# Micro_V6.net
KiCad netlist of a schematic drawn in EAGLE
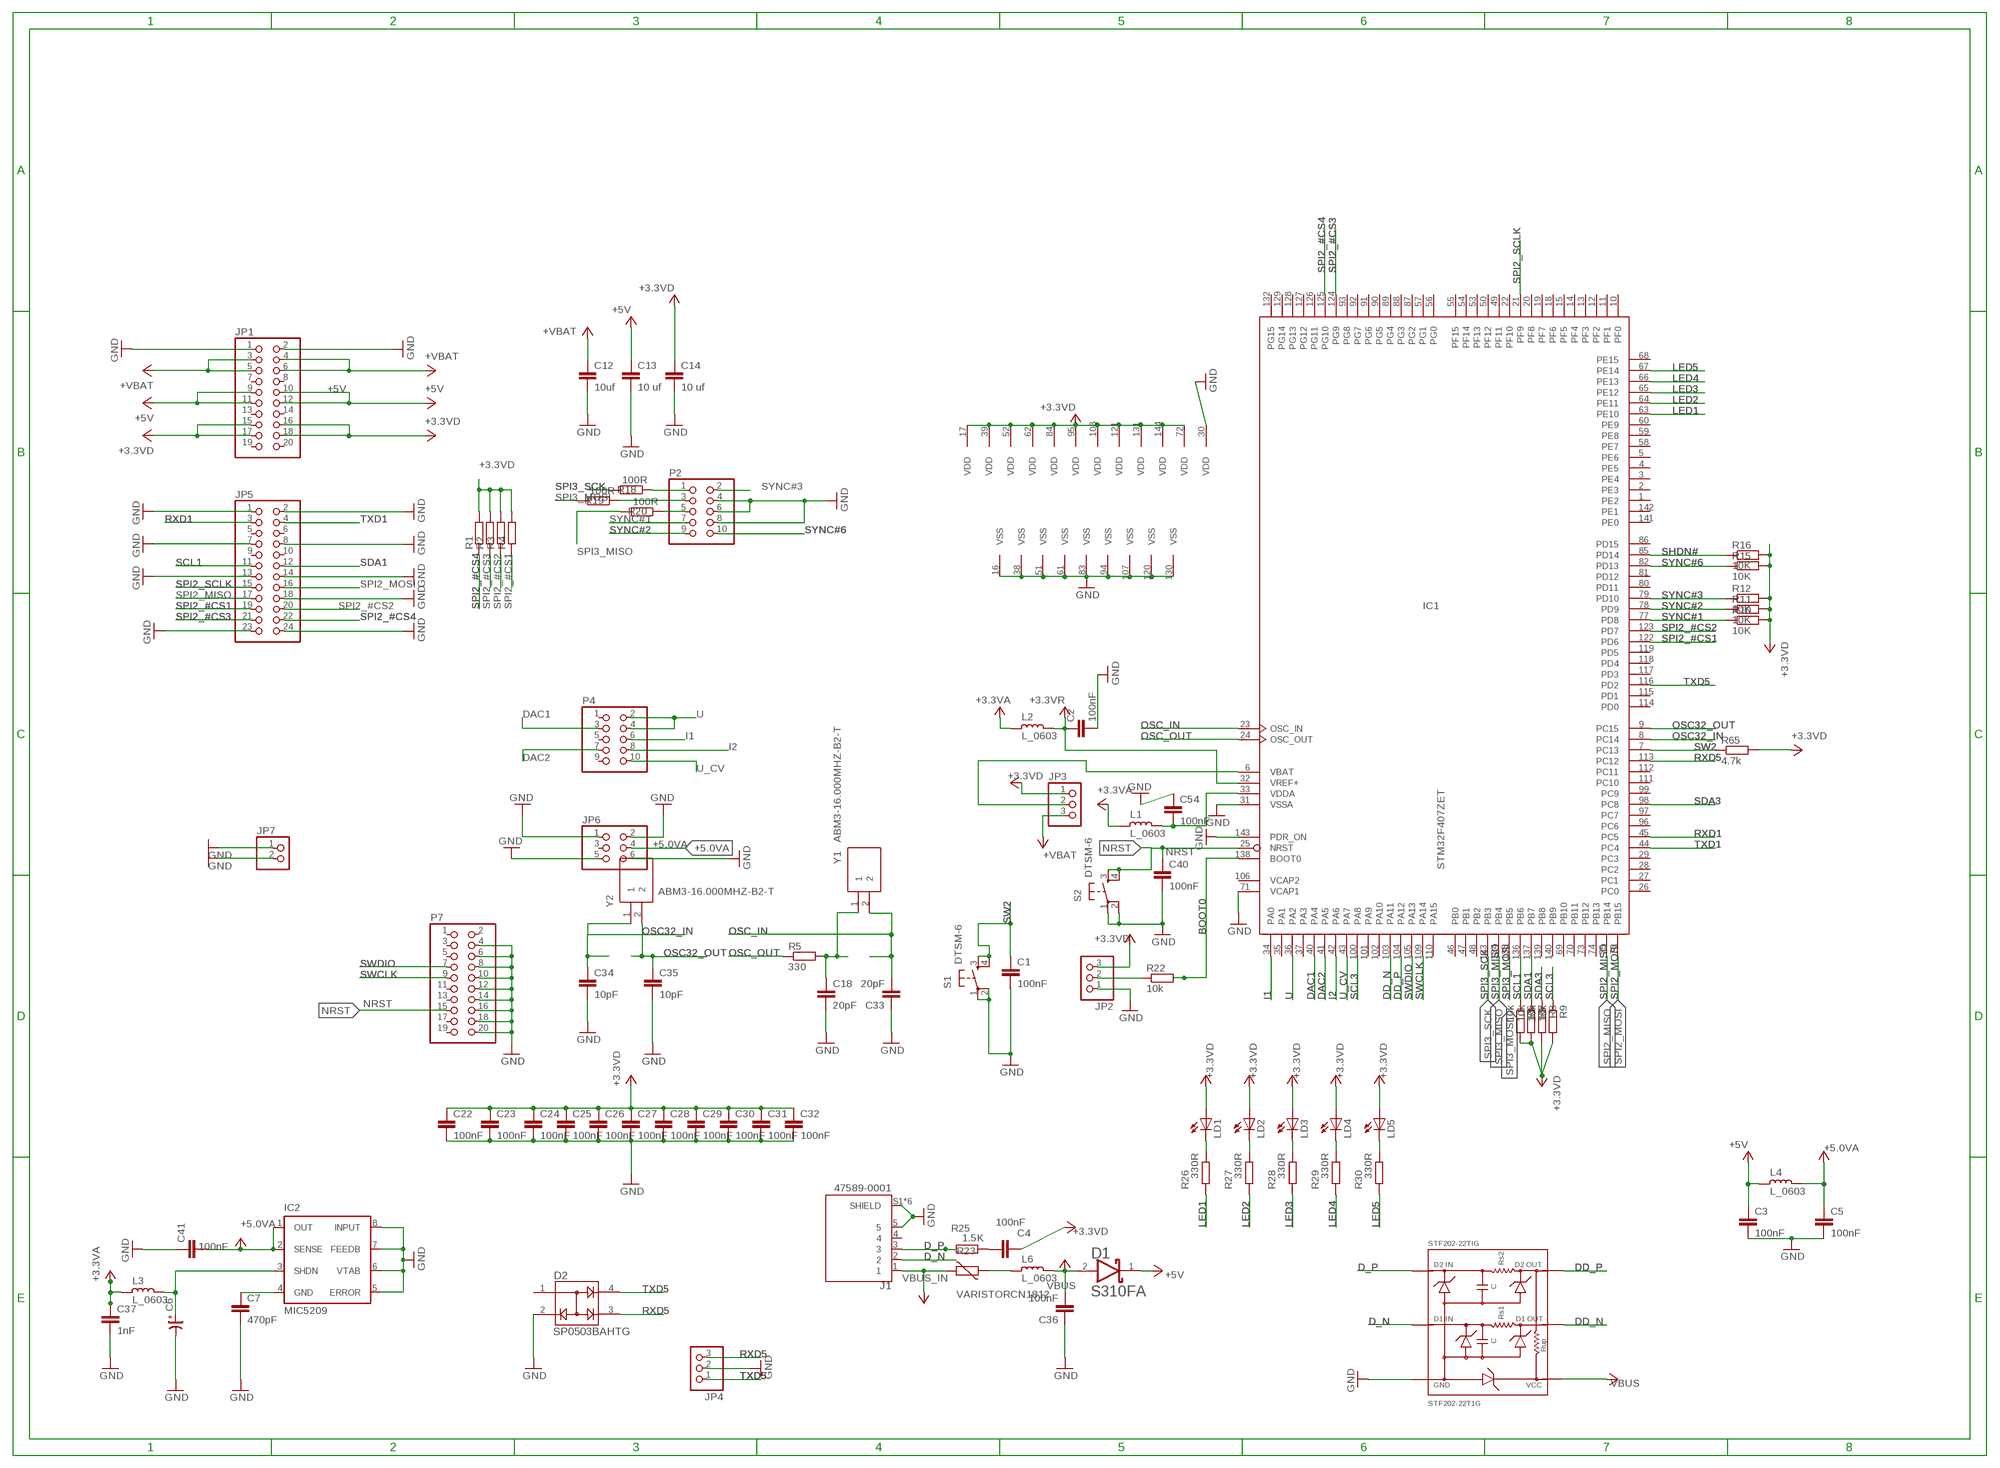
[diagram p0: schematic, sheet 1]

(export (version "E")
  (design (tool "Eeschema 10.0.6"))
  (components
    (comp (ref "C1")
      (value "100nF")
      (footprint "eagle-import:C0805")
      (libsource (lib "eagle-import") (part "C-EUC0805"))
    )
    (comp (ref "C2")
      (value "100nF")
      (footprint "eagle-import:C0805")
      (libsource (lib "eagle-import") (part "C-EUC0805"))
    )
    (comp (ref "C3")
      (value "100nF")
      (footprint "eagle-import:C0805")
      (libsource (lib "eagle-import") (part "C-EUC0805"))
    )
    (comp (ref "C4")
      (value "100nF")
      (footprint "eagle-import:C0805")
      (libsource (lib "eagle-import") (part "C-EUC0805"))
    )
    (comp (ref "C5")
      (value "100nF")
      (footprint "eagle-import:C0805")
      (libsource (lib "eagle-import") (part "C-EUC0805"))
    )
    (comp (ref "C6")
      (value "CP_SV-A")
      (footprint "eagle-import:CSV-A")
      (libsource (lib "eagle-import") (part "CP_SV-A"))
    )
    (comp (ref "C7")
      (value "470pF")
      (footprint "eagle-import:C0805")
      (libsource (lib "eagle-import") (part "C-EUC0805"))
    )
    (comp (ref "C12")
      (value "10uf")
      (footprint "eagle-import:C0805K")
      (libsource (lib "eagle-import") (part "C-EUC0805K"))
    )
    (comp (ref "C13")
      (value "10 uf")
      (footprint "eagle-import:C0805K")
      (libsource (lib "eagle-import") (part "C-EUC0805K"))
    )
    (comp (ref "C14")
      (value "10 uf")
      (footprint "eagle-import:C0805K")
      (libsource (lib "eagle-import") (part "C-EUC0805K"))
    )
    (comp (ref "C18")
      (value "20pF")
      (footprint "eagle-import:C0805")
      (libsource (lib "eagle-import") (part "C-EUC0805"))
    )
    (comp (ref "C22")
      (value "100nF")
      (footprint "eagle-import:C0805")
      (libsource (lib "eagle-import") (part "C-EUC0805"))
    )
    (comp (ref "C23")
      (value "100nF")
      (footprint "eagle-import:C0805")
      (libsource (lib "eagle-import") (part "C-EUC0805"))
    )
    (comp (ref "C24")
      (value "100nF")
      (footprint "eagle-import:C0805")
      (libsource (lib "eagle-import") (part "C-EUC0805"))
    )
    (comp (ref "C25")
      (value "100nF")
      (footprint "eagle-import:C0805")
      (libsource (lib "eagle-import") (part "C-EUC0805"))
    )
    (comp (ref "C26")
      (value "100nF")
      (footprint "eagle-import:C0805")
      (libsource (lib "eagle-import") (part "C-EUC0805"))
    )
    (comp (ref "C27")
      (value "100nF")
      (footprint "eagle-import:C0805")
      (libsource (lib "eagle-import") (part "C-EUC0805"))
    )
    (comp (ref "C28")
      (value "100nF")
      (footprint "eagle-import:C0805")
      (libsource (lib "eagle-import") (part "C-EUC0805"))
    )
    (comp (ref "C29")
      (value "100nF")
      (footprint "eagle-import:C0805")
      (libsource (lib "eagle-import") (part "C-EUC0805"))
    )
    (comp (ref "C30")
      (value "100nF")
      (footprint "eagle-import:C0805")
      (libsource (lib "eagle-import") (part "C-EUC0805"))
    )
    (comp (ref "C31")
      (value "100nF")
      (footprint "eagle-import:C0805")
      (libsource (lib "eagle-import") (part "C-EUC0805"))
    )
    (comp (ref "C32")
      (value "100nF")
      (footprint "eagle-import:C0805")
      (libsource (lib "eagle-import") (part "C-EUC0805"))
    )
    (comp (ref "C33")
      (value "20pF")
      (footprint "eagle-import:C0805")
      (libsource (lib "eagle-import") (part "C-EUC0805"))
    )
    (comp (ref "C34")
      (value "10pF")
      (footprint "eagle-import:C0805")
      (libsource (lib "eagle-import") (part "C-EUC0805"))
    )
    (comp (ref "C35")
      (value "10pF")
      (footprint "eagle-import:C0805")
      (libsource (lib "eagle-import") (part "C-EUC0805"))
    )
    (comp (ref "C36")
      (value "100nF")
      (footprint "eagle-import:C0805")
      (libsource (lib "eagle-import") (part "C-EUC0805"))
    )
    (comp (ref "C37")
      (value "1nF")
      (footprint "eagle-import:C0805")
      (libsource (lib "eagle-import") (part "C-EUC0805"))
    )
    (comp (ref "C40")
      (value "100nF")
      (footprint "eagle-import:C0805")
      (libsource (lib "eagle-import") (part "C-EUC0805"))
    )
    (comp (ref "C41")
      (value "100nF")
      (footprint "eagle-import:C0805")
      (libsource (lib "eagle-import") (part "C-EUC0805"))
    )
    (comp (ref "C54")
      (value "100nF")
      (footprint "eagle-import:C0805")
      (libsource (lib "eagle-import") (part "C-EUC0805"))
    )
    (comp (ref "D1")
      (value "ON_SEMICONDUCTOR_S310FAON_SEMICONDUCTOR_S310FA_0_0")
      (footprint "eagle-import:ON_SEMICONDUCTOR_S310FA_0")
      (fields
        (field (name "DIGIKEY_PART_NUMBER") "S310FACT-ND")
        (field (name "MF") "ON Semiconductor")
        (field (name "MOUSER_PART_NUMBER") "512-S310FA")
      )
      (libsource (lib "eagle-import") (part "ON_SEMICONDUCTOR_S310FAON_SEMICONDUCTOR_S310FA_0_0"))
    )
    (comp (ref "D2")
      (value "SP0503BAHTG")
      (footprint "eagle-import:SOT143")
      (fields (field (name "MF") "Littelfuse Inc."))
      (libsource (lib "eagle-import") (part "SP0503BAHTG"))
    )
    (comp (ref "IC1")
      (value "STM32F407ZET")
      (footprint "eagle-import:LQFP144")
      (libsource (lib "eagle-import") (part "STM32F407ZTE"))
    )
    (comp (ref "IC2")
      (value "MIC5209")
      (footprint "eagle-import:SO-08")
      (libsource (lib "eagle-import") (part "LP2951?ACM-3.3"))
    )
    (comp (ref "J1")
      (value "47589-0001")
      (footprint "eagle-import:MOLEX_47589-0001")
      (fields (field (name "MF") "Molex"))
      (libsource (lib "eagle-import") (part "47589-0001"))
    )
    (comp (ref "JP1")
      (value "PINHD-2X10")
      (footprint "eagle-import:2X10")
      (libsource (lib "eagle-import") (part "PINHD-2X10"))
    )
    (comp (ref "JP2")
      (value "PINHD-1X3")
      (footprint "eagle-import:1X03")
      (libsource (lib "eagle-import") (part "PINHD-1X3"))
    )
    (comp (ref "JP3")
      (value "PINHD-1X3")
      (footprint "eagle-import:1X03")
      (libsource (lib "eagle-import") (part "PINHD-1X3"))
    )
    (comp (ref "JP4")
      (value "PINHD-1X3")
      (footprint "eagle-import:1X03")
      (libsource (lib "eagle-import") (part "PINHD-1X3"))
    )
    (comp (ref "JP5")
      (value "PINHD-2X12")
      (footprint "eagle-import:2X12")
      (libsource (lib "eagle-import") (part "PINHD-2X12"))
    )
    (comp (ref "JP6")
      (value "PINHD-2X3")
      (footprint "eagle-import:2X03")
      (libsource (lib "eagle-import") (part "PINHD-2X3"))
    )
    (comp (ref "JP7")
      (value "PINHD-1X2")
      (footprint "eagle-import:1X02")
      (libsource (lib "eagle-import") (part "PINHD-1X2"))
    )
    (comp (ref "L1")
      (value "L_0603")
      (footprint "eagle-import:L0603")
      (libsource (lib "eagle-import") (part "L_0603"))
    )
    (comp (ref "L2")
      (value "L_0603")
      (footprint "eagle-import:L0603")
      (libsource (lib "eagle-import") (part "L_0603"))
    )
    (comp (ref "L3")
      (value "L_0603")
      (footprint "eagle-import:L0603")
      (libsource (lib "eagle-import") (part "L_0603"))
    )
    (comp (ref "L4")
      (value "L_0603")
      (footprint "eagle-import:L0603")
      (libsource (lib "eagle-import") (part "L_0603"))
    )
    (comp (ref "L6")
      (value "L_0603")
      (footprint "eagle-import:L0603")
      (libsource (lib "eagle-import") (part "L_0603"))
    )
    (comp (ref "LD1")
      (value "LEDSMT1206")
      (footprint "eagle-import:1206")
      (libsource (lib "eagle-import") (part "LEDSMT1206"))
    )
    (comp (ref "LD2")
      (value "LEDSMT1206")
      (footprint "eagle-import:1206")
      (libsource (lib "eagle-import") (part "LEDSMT1206"))
    )
    (comp (ref "LD3")
      (value "LEDSMT1206")
      (footprint "eagle-import:1206")
      (libsource (lib "eagle-import") (part "LEDSMT1206"))
    )
    (comp (ref "LD4")
      (value "LEDSMT1206")
      (footprint "eagle-import:1206")
      (libsource (lib "eagle-import") (part "LEDSMT1206"))
    )
    (comp (ref "LD5")
      (value "LEDSMT1206")
      (footprint "eagle-import:1206")
      (libsource (lib "eagle-import") (part "LEDSMT1206"))
    )
    (comp (ref "P2")
      (value "PINHD-2X5")
      (footprint "eagle-import:2X05")
      (libsource (lib "eagle-import") (part "PINHD-2X5"))
    )
    (comp (ref "P4")
      (value "PINHD-2X5")
      (footprint "eagle-import:2X05")
      (libsource (lib "eagle-import") (part "PINHD-2X5"))
    )
    (comp (ref "P7")
      (value "PINHD-2X10")
      (footprint "eagle-import:2X10")
      (libsource (lib "eagle-import") (part "PINHD-2X10"))
    )
    (comp (ref "R1")
      (value "R-EU_R0603")
      (footprint "eagle-import:R0603")
      (libsource (lib "eagle-import") (part "R-EU_R0603"))
    )
    (comp (ref "R2")
      (value "R-EU_R0603")
      (footprint "eagle-import:R0603")
      (libsource (lib "eagle-import") (part "R-EU_R0603"))
    )
    (comp (ref "R3")
      (value "R-EU_R0603")
      (footprint "eagle-import:R0603")
      (libsource (lib "eagle-import") (part "R-EU_R0603"))
    )
    (comp (ref "R4")
      (value "R-EU_R0603")
      (footprint "eagle-import:R0603")
      (libsource (lib "eagle-import") (part "R-EU_R0603"))
    )
    (comp (ref "R5")
      (value "330")
      (footprint "eagle-import:R0603")
      (libsource (lib "eagle-import") (part "R-EU_R0603"))
    )
    (comp (ref "R6")
      (value "10k")
      (footprint "eagle-import:R0603")
      (libsource (lib "eagle-import") (part "R-EU_R0603"))
    )
    (comp (ref "R7")
      (value "10k")
      (footprint "eagle-import:R0603")
      (libsource (lib "eagle-import") (part "R-EU_R0603"))
    )
    (comp (ref "R8")
      (value "10k")
      (footprint "eagle-import:R0603")
      (libsource (lib "eagle-import") (part "R-EU_R0603"))
    )
    (comp (ref "R9")
      (value "10k")
      (footprint "eagle-import:R0603")
      (libsource (lib "eagle-import") (part "R-EU_R0603"))
    )
    (comp (ref "R10")
      (value "10K")
      (footprint "eagle-import:R0603")
      (libsource (lib "eagle-import") (part "R-EU_R0603"))
    )
    (comp (ref "R11")
      (value "10K")
      (footprint "eagle-import:R0603")
      (libsource (lib "eagle-import") (part "R-EU_R0603"))
    )
    (comp (ref "R12")
      (value "10K")
      (footprint "eagle-import:R0603")
      (libsource (lib "eagle-import") (part "R-EU_R0603"))
    )
    (comp (ref "R15")
      (value "10K")
      (footprint "eagle-import:R0603")
      (libsource (lib "eagle-import") (part "R-EU_R0603"))
    )
    (comp (ref "R16")
      (value "10K")
      (footprint "eagle-import:R0603")
      (libsource (lib "eagle-import") (part "R-EU_R0603"))
    )
    (comp (ref "R18")
      (value "100R")
      (footprint "eagle-import:R0603")
      (libsource (lib "eagle-import") (part "R-EU_R0603"))
    )
    (comp (ref "R19")
      (value "100R")
      (footprint "eagle-import:R0603")
      (libsource (lib "eagle-import") (part "R-EU_R0603"))
    )
    (comp (ref "R20")
      (value "100R")
      (footprint "eagle-import:R0603")
      (libsource (lib "eagle-import") (part "R-EU_R0603"))
    )
    (comp (ref "R22")
      (value "10k")
      (footprint "eagle-import:R0603")
      (libsource (lib "eagle-import") (part "R-EU_R0603"))
    )
    (comp (ref "R23")
      (value "VARISTORCN1812")
      (footprint "eagle-import:CT_CN1812")
      (libsource (lib "eagle-import") (part "VARISTORCN1812"))
    )
    (comp (ref "R25")
      (value "1.5K")
      (footprint "eagle-import:R0603")
      (libsource (lib "eagle-import") (part "R-EU_R0603"))
    )
    (comp (ref "R26")
      (value "330R")
      (footprint "eagle-import:R0603")
      (libsource (lib "eagle-import") (part "R-EU_R0603"))
    )
    (comp (ref "R27")
      (value "330R")
      (footprint "eagle-import:R0603")
      (libsource (lib "eagle-import") (part "R-EU_R0603"))
    )
    (comp (ref "R28")
      (value "330R")
      (footprint "eagle-import:R0603")
      (libsource (lib "eagle-import") (part "R-EU_R0603"))
    )
    (comp (ref "R29")
      (value "330R")
      (footprint "eagle-import:R0603")
      (libsource (lib "eagle-import") (part "R-EU_R0603"))
    )
    (comp (ref "R30")
      (value "330R")
      (footprint "eagle-import:R0603")
      (libsource (lib "eagle-import") (part "R-EU_R0603"))
    )
    (comp (ref "R65")
      (value "4.7k")
      (footprint "eagle-import:R0603")
      (libsource (lib "eagle-import") (part "R-EU_R0603"))
    )
    (comp (ref "S1")
      (value "DTSM-6")
      (footprint "eagle-import:DTSM-6")
      (libsource (lib "eagle-import") (part "DTSM-6"))
    )
    (comp (ref "S2")
      (value "DTSM-6")
      (footprint "eagle-import:DTSM-6")
      (libsource (lib "eagle-import") (part "DTSM-6"))
    )
    (comp (ref "STF202-22TIG")
      (value "STF202-22T1G")
      (footprint "eagle-import:STF202-22T1G")
      (fields (field (name "MF") "ON Semiconductor"))
      (libsource (lib "eagle-import") (part "STF202-22T1G"))
    )
    (comp (ref "Y1")
      (value "ABM3-16.000MHZ-B2-T")
      (footprint "eagle-import:ABM316000MHZB2T")
      (fields (field (name "MOUSER_PART_NUMBER") "815-ABM3-16-B2-T"))
      (libsource (lib "eagle-import") (part "ABM3-16.000MHZ-B2-T"))
    )
    (comp (ref "Y2")
      (value "ABM3-16.000MHZ-B2-T")
      (footprint "eagle-import:ABM316000MHZB2T")
      (fields (field (name "MOUSER_PART_NUMBER") "815-ABM3-16-B2-T"))
      (libsource (lib "eagle-import") (part "ABM3-16.000MHZ-B2-T"))
    )
  )
  (nets
    (net (code "1") (name "+3.3VA") (class "Default")
      (node (ref "C37") (pin "1") (pinfunction "1_1") (pintype "passive"))
      (node (ref "L1") (pin "2") (pinfunction "2_2") (pintype "passive"))
      (node (ref "L2") (pin "2") (pinfunction "2_2") (pintype "passive"))
      (node (ref "L3") (pin "2") (pinfunction "2_2") (pintype "passive"))
    )
    (net (code "2") (name "+3.3VD") (class "Default")
      (node (ref "C14") (pin "1") (pinfunction "1_1") (pintype "passive"))
      (node (ref "C22") (pin "1") (pinfunction "1_1") (pintype "passive"))
      (node (ref "C23") (pin "1") (pinfunction "1_1") (pintype "passive"))
      (node (ref "C24") (pin "1") (pinfunction "1_1") (pintype "passive"))
      (node (ref "C25") (pin "1") (pinfunction "1_1") (pintype "passive"))
      (node (ref "C26") (pin "1") (pinfunction "1_1") (pintype "passive"))
      (node (ref "C27") (pin "1") (pinfunction "1_1") (pintype "passive"))
      (node (ref "C28") (pin "1") (pinfunction "1_1") (pintype "passive"))
      (node (ref "C29") (pin "1") (pinfunction "1_1") (pintype "passive"))
      (node (ref "C30") (pin "1") (pinfunction "1_1") (pintype "passive"))
      (node (ref "C31") (pin "1") (pinfunction "1_1") (pintype "passive"))
      (node (ref "C32") (pin "1") (pinfunction "1_1") (pintype "passive"))
      (node (ref "C4") (pin "1") (pinfunction "1_1") (pintype "passive"))
      (node (ref "IC1") (pin "108") (pinfunction "VDD_108") (pintype "power_in"))
      (node (ref "IC1") (pin "121") (pinfunction "VDD_121") (pintype "power_in"))
      (node (ref "IC1") (pin "131") (pinfunction "VDD_131") (pintype "power_in"))
      (node (ref "IC1") (pin "144") (pinfunction "VDD_144") (pintype "power_in"))
      (node (ref "IC1") (pin "17") (pinfunction "VDD_17") (pintype "power_in"))
      (node (ref "IC1") (pin "39") (pinfunction "VDD_39") (pintype "power_in"))
      (node (ref "IC1") (pin "52") (pinfunction "VDD_52") (pintype "power_in"))
      (node (ref "IC1") (pin "62") (pinfunction "VDD_62") (pintype "power_in"))
      (node (ref "IC1") (pin "72") (pinfunction "VDD_72") (pintype "power_in"))
      (node (ref "IC1") (pin "84") (pinfunction "VDD_84") (pintype "power_in"))
      (node (ref "IC1") (pin "95") (pinfunction "VDD_95") (pintype "power_in"))
      (node (ref "JP1") (pin "15") (pinfunction "15_15") (pintype "passive"))
      (node (ref "JP1") (pin "16") (pinfunction "16_16") (pintype "passive"))
      (node (ref "JP1") (pin "17") (pinfunction "17_17") (pintype "passive"))
      (node (ref "JP1") (pin "18") (pinfunction "18_18") (pintype "passive"))
      (node (ref "JP2") (pin "3") (pinfunction "3_3") (pintype "passive"))
      (node (ref "JP3") (pin "1") (pinfunction "1_1") (pintype "passive"))
      (node (ref "LD1") (pin "A") (pinfunction "A_A") (pintype "passive"))
      (node (ref "LD2") (pin "A") (pinfunction "A_A") (pintype "passive"))
      (node (ref "LD3") (pin "A") (pinfunction "A_A") (pintype "passive"))
      (node (ref "LD4") (pin "A") (pinfunction "A_A") (pintype "passive"))
      (node (ref "LD5") (pin "A") (pinfunction "A_A") (pintype "passive"))
      (node (ref "R1") (pin "2") (pinfunction "2_2") (pintype "passive"))
      (node (ref "R10") (pin "2") (pinfunction "2_2") (pintype "passive"))
      (node (ref "R11") (pin "2") (pinfunction "2_2") (pintype "passive"))
      (node (ref "R12") (pin "2") (pinfunction "2_2") (pintype "passive"))
      (node (ref "R15") (pin "2") (pinfunction "2_2") (pintype "passive"))
      (node (ref "R16") (pin "2") (pinfunction "2_2") (pintype "passive"))
      (node (ref "R2") (pin "2") (pinfunction "2_2") (pintype "passive"))
      (node (ref "R3") (pin "2") (pinfunction "2_2") (pintype "passive"))
      (node (ref "R4") (pin "2") (pinfunction "2_2") (pintype "passive"))
      (node (ref "R6") (pin "2") (pinfunction "2_2") (pintype "passive"))
      (node (ref "R65") (pin "2") (pinfunction "2_2") (pintype "passive"))
      (node (ref "R7") (pin "2") (pinfunction "2_2") (pintype "passive"))
      (node (ref "R8") (pin "2") (pinfunction "2_2") (pintype "passive"))
      (node (ref "R9") (pin "2") (pinfunction "2_2") (pintype "passive"))
    )
    (net (code "3") (name "+3.3VR") (class "Default")
      (node (ref "C2") (pin "1") (pinfunction "1_1") (pintype "passive"))
      (node (ref "IC1") (pin "32") (pinfunction "VREF+_32") (pintype "power_in"))
      (node (ref "L2") (pin "1") (pinfunction "1_1") (pintype "passive"))
    )
    (net (code "4") (name "+5.0VA") (class "Default")
      (node (ref "C41") (pin "2") (pinfunction "2_2") (pintype "passive"))
      (node (ref "C5") (pin "1") (pinfunction "1_1") (pintype "passive"))
      (node (ref "IC2") (pin "1") (pinfunction "OUT_1") (pintype "output"))
      (node (ref "IC2") (pin "2") (pinfunction "SENSE_2") (pintype "input"))
      (node (ref "JP6") (pin "4") (pinfunction "4_4") (pintype "passive"))
      (node (ref "L4") (pin "1") (pinfunction "1_1") (pintype "passive"))
    )
    (net (code "5") (name "+5V") (class "Default")
      (node (ref "C13") (pin "1") (pinfunction "1_1") (pintype "passive"))
      (node (ref "C3") (pin "1") (pinfunction "1_1") (pintype "passive"))
      (node (ref "D1") (pin "1") (pinfunction "CATHODE_1") (pintype "passive"))
      (node (ref "JP1") (pin "10") (pinfunction "10_10") (pintype "passive"))
      (node (ref "JP1") (pin "11") (pinfunction "11_11") (pintype "passive"))
      (node (ref "JP1") (pin "12") (pinfunction "12_12") (pintype "passive"))
      (node (ref "JP1") (pin "9") (pinfunction "9_9") (pintype "passive"))
      (node (ref "L4") (pin "2") (pinfunction "2_2") (pintype "passive"))
    )
    (net (code "6") (name "+VBAT") (class "Default")
      (node (ref "C12") (pin "1") (pinfunction "1_1") (pintype "passive"))
      (node (ref "JP1") (pin "3") (pinfunction "3_3") (pintype "passive"))
      (node (ref "JP1") (pin "4") (pinfunction "4_4") (pintype "passive"))
      (node (ref "JP1") (pin "5") (pinfunction "5_5") (pintype "passive"))
      (node (ref "JP1") (pin "6") (pinfunction "6_6") (pintype "passive"))
      (node (ref "JP3") (pin "3") (pinfunction "3_3") (pintype "passive"))
    )
    (net (code "7") (name "/BOOT0") (class "Default")
      (node (ref "IC1") (pin "138") (pinfunction "BOOT0_138") (pintype "input"))
      (node (ref "R22") (pin "2") (pinfunction "2_2") (pintype "passive"))
    )
    (net (code "8") (name "/DAC1") (class "Default")
      (node (ref "IC1") (pin "40") (pinfunction "PA4_40") (pintype "bidirectional"))
      (node (ref "P4") (pin "3") (pinfunction "3_3") (pintype "passive"))
    )
    (net (code "9") (name "/DAC2") (class "Default")
      (node (ref "IC1") (pin "41") (pinfunction "PA5_41") (pintype "bidirectional"))
      (node (ref "P4") (pin "7") (pinfunction "7_7") (pintype "passive"))
    )
    (net (code "10") (name "/DD_N") (class "Default")
      (node (ref "IC1") (pin "103") (pinfunction "PA11_103") (pintype "bidirectional"))
      (node (ref "STF202-22TIG") (pin "2") (pinfunction "D1-IN_2") (pintype "bidirectional"))
    )
    (net (code "11") (name "/DD_P") (class "Default")
      (node (ref "IC1") (pin "104") (pinfunction "PA12_104") (pintype "bidirectional"))
      (node (ref "STF202-22TIG") (pin "3") (pinfunction "D2-IN_3") (pintype "bidirectional"))
    )
    (net (code "12") (name "/D_N") (class "Default")
      (node (ref "J1") (pin "2") (pinfunction "2_2") (pintype "passive"))
      (node (ref "STF202-22TIG") (pin "5") (pinfunction "D1-OUT_5") (pintype "bidirectional"))
    )
    (net (code "13") (name "/D_P") (class "Default")
      (node (ref "J1") (pin "3") (pinfunction "3_3") (pintype "passive"))
      (node (ref "R25") (pin "1") (pinfunction "1_1") (pintype "passive"))
      (node (ref "STF202-22TIG") (pin "4") (pinfunction "D2-OUT_4") (pintype "bidirectional"))
    )
    (net (code "14") (name "/I1") (class "Default")
      (node (ref "IC1") (pin "34") (pinfunction "PA0_34") (pintype "bidirectional"))
      (node (ref "P4") (pin "6") (pinfunction "6_6") (pintype "passive"))
    )
    (net (code "15") (name "/I2") (class "Default")
      (node (ref "IC1") (pin "42") (pinfunction "PA6_42") (pintype "bidirectional"))
      (node (ref "P4") (pin "8") (pinfunction "8_8") (pintype "passive"))
    )
    (net (code "16") (name "/LED1") (class "Default")
      (node (ref "IC1") (pin "63") (pinfunction "PE10_63") (pintype "bidirectional"))
      (node (ref "R26") (pin "1") (pinfunction "1_1") (pintype "passive"))
    )
    (net (code "17") (name "/LED2") (class "Default")
      (node (ref "IC1") (pin "64") (pinfunction "PE11_64") (pintype "bidirectional"))
      (node (ref "R27") (pin "1") (pinfunction "1_1") (pintype "passive"))
    )
    (net (code "18") (name "/LED3") (class "Default")
      (node (ref "IC1") (pin "65") (pinfunction "PE12_65") (pintype "bidirectional"))
      (node (ref "R28") (pin "1") (pinfunction "1_1") (pintype "passive"))
    )
    (net (code "19") (name "/LED4") (class "Default")
      (node (ref "IC1") (pin "66") (pinfunction "PE13_66") (pintype "bidirectional"))
      (node (ref "R29") (pin "1") (pinfunction "1_1") (pintype "passive"))
    )
    (net (code "20") (name "/LED5") (class "Default")
      (node (ref "IC1") (pin "67") (pinfunction "PE14_67") (pintype "bidirectional"))
      (node (ref "R30") (pin "1") (pinfunction "1_1") (pintype "passive"))
    )
    (net (code "21") (name "/OSC32_IN") (class "Default")
      (node (ref "C34") (pin "1") (pinfunction "1_1") (pintype "passive"))
      (node (ref "IC1") (pin "8") (pinfunction "PC14_8") (pintype "bidirectional"))
      (node (ref "Y2") (pin "1") (pinfunction "1_1") (pintype "bidirectional"))
    )
    (net (code "22") (name "/OSC32_OUT") (class "Default")
      (node (ref "C35") (pin "1") (pinfunction "1_1") (pintype "passive"))
      (node (ref "IC1") (pin "9") (pinfunction "PC15_9") (pintype "bidirectional"))
      (node (ref "Y2") (pin "2") (pinfunction "2_2") (pintype "bidirectional"))
    )
    (net (code "23") (name "/OSC_IN") (class "Default")
      (node (ref "C33") (pin "2") (pinfunction "2_2") (pintype "passive"))
      (node (ref "IC1") (pin "23") (pinfunction "OSC_IN_23") (pintype "bidirectional"))
      (node (ref "Y1") (pin "2") (pinfunction "2_2") (pintype "bidirectional"))
    )
    (net (code "24") (name "/OSC_OUT") (class "Default")
      (node (ref "IC1") (pin "24") (pinfunction "OSC_OUT_24") (pintype "bidirectional"))
      (node (ref "R5") (pin "1") (pinfunction "1_1") (pintype "passive"))
    )
    (net (code "25") (name "/RXD1") (class "Default")
      (node (ref "IC1") (pin "45") (pinfunction "PC5_45") (pintype "bidirectional"))
      (node (ref "JP5") (pin "3") (pinfunction "3_3") (pintype "passive"))
    )
    (net (code "26") (name "/RXD5") (class "Default")
      (node (ref "D2") (pin "3") (pinfunction "3_3") (pintype "passive"))
      (node (ref "IC1") (pin "113") (pinfunction "PC12_113") (pintype "bidirectional"))
      (node (ref "JP4") (pin "3") (pinfunction "3_3") (pintype "passive"))
    )
    (net (code "27") (name "/SCL1") (class "Default")
      (node (ref "IC1") (pin "136") (pinfunction "PB6_136") (pintype "bidirectional"))
      (node (ref "JP5") (pin "11") (pinfunction "11_11") (pintype "passive"))
      (node (ref "R6") (pin "1") (pinfunction "1_1") (pintype "passive"))
    )
    (net (code "28") (name "/SCL3") (class "Default")
      (node (ref "IC1") (pin "100") (pinfunction "PA8_100") (pintype "bidirectional"))
      (node (ref "R9") (pin "1") (pinfunction "1_1") (pintype "passive"))
    )
    (net (code "29") (name "/SDA1") (class "Default")
      (node (ref "IC1") (pin "137") (pinfunction "PB7_137") (pintype "bidirectional"))
      (node (ref "JP5") (pin "12") (pinfunction "12_12") (pintype "passive"))
      (node (ref "R7") (pin "1") (pinfunction "1_1") (pintype "passive"))
    )
    (net (code "30") (name "/SDA3") (class "Default")
      (node (ref "IC1") (pin "98") (pinfunction "PC8_98") (pintype "bidirectional"))
      (node (ref "R8") (pin "1") (pinfunction "1_1") (pintype "passive"))
    )
    (net (code "31") (name "/SHDN#") (class "Default")
      (node (ref "IC1") (pin "85") (pinfunction "PD14_85") (pintype "bidirectional"))
      (node (ref "R16") (pin "1") (pinfunction "1_1") (pintype "passive"))
    )
    (net (code "32") (name "/SPI2_#CS1") (class "Default")
      (node (ref "IC1") (pin "122") (pinfunction "PD6_122") (pintype "bidirectional"))
      (node (ref "JP5") (pin "19") (pinfunction "19_19") (pintype "passive"))
      (node (ref "R4") (pin "1") (pinfunction "1_1") (pintype "passive"))
    )
    (net (code "33") (name "/SPI2_#CS2") (class "Default")
      (node (ref "IC1") (pin "123") (pinfunction "PD7_123") (pintype "bidirectional"))
      (node (ref "JP5") (pin "20") (pinfunction "20_20") (pintype "passive"))
      (node (ref "R3") (pin "1") (pinfunction "1_1") (pintype "passive"))
    )
    (net (code "34") (name "/SPI2_#CS3") (class "Default")
      (node (ref "IC1") (pin "124") (pinfunction "PG9_124") (pintype "bidirectional"))
      (node (ref "JP5") (pin "21") (pinfunction "21_21") (pintype "passive"))
      (node (ref "R2") (pin "1") (pinfunction "1_1") (pintype "passive"))
    )
    (net (code "35") (name "/SPI2_#CS4") (class "Default")
      (node (ref "IC1") (pin "125") (pinfunction "PG10_125") (pintype "bidirectional"))
      (node (ref "JP5") (pin "22") (pinfunction "22_22") (pintype "passive"))
      (node (ref "R1") (pin "1") (pinfunction "1_1") (pintype "passive"))
    )
    (net (code "36") (name "/SPI2_SCLK") (class "Default")
      (node (ref "IC1") (pin "21") (pinfunction "PF9_21") (pintype "bidirectional"))
      (node (ref "JP5") (pin "15") (pinfunction "15_15") (pintype "passive"))
    )
    (net (code "37") (name "/SW2") (class "Default")
      (node (ref "C1") (pin "1") (pinfunction "1_1") (pintype "passive"))
      (node (ref "IC1") (pin "7") (pinfunction "PC13_7") (pintype "bidirectional"))
      (node (ref "R65") (pin "1") (pinfunction "1_1") (pintype "passive"))
      (node (ref "S1") (pin "3") (pinfunction "3_3") (pintype "passive"))
      (node (ref "S1") (pin "4") (pinfunction "4_4") (pintype "passive"))
    )
    (net (code "38") (name "/SWCLK") (class "Default")
      (node (ref "IC1") (pin "109") (pinfunction "PA14_109") (pintype "bidirectional"))
      (node (ref "P7") (pin "9") (pinfunction "9_9") (pintype "passive"))
    )
    (net (code "39") (name "/SWDIO") (class "Default")
      (node (ref "IC1") (pin "105") (pinfunction "PA13_105") (pintype "bidirectional"))
      (node (ref "P7") (pin "7") (pinfunction "7_7") (pintype "passive"))
    )
    (net (code "40") (name "/SYNC#1") (class "Default")
      (node (ref "IC1") (pin "77") (pinfunction "PD8_77") (pintype "bidirectional"))
      (node (ref "P2") (pin "7") (pinfunction "7_7") (pintype "passive"))
      (node (ref "R10") (pin "1") (pinfunction "1_1") (pintype "passive"))
    )
    (net (code "41") (name "/SYNC#2") (class "Default")
      (node (ref "IC1") (pin "78") (pinfunction "PD9_78") (pintype "bidirectional"))
      (node (ref "P2") (pin "9") (pinfunction "9_9") (pintype "passive"))
      (node (ref "R11") (pin "1") (pinfunction "1_1") (pintype "passive"))
    )
    (net (code "42") (name "/SYNC#3") (class "Default")
      (node (ref "IC1") (pin "79") (pinfunction "PD10_79") (pintype "bidirectional"))
      (node (ref "P2") (pin "2") (pinfunction "2_2") (pintype "passive"))
      (node (ref "R12") (pin "1") (pinfunction "1_1") (pintype "passive"))
    )
    (net (code "43") (name "/SYNC#6") (class "Default")
      (node (ref "IC1") (pin "82") (pinfunction "PD13_82") (pintype "bidirectional"))
      (node (ref "P2") (pin "10") (pinfunction "10_10") (pintype "passive"))
      (node (ref "R15") (pin "1") (pinfunction "1_1") (pintype "passive"))
    )
    (net (code "44") (name "/TXD1") (class "Default")
      (node (ref "IC1") (pin "44") (pinfunction "PC4_44") (pintype "bidirectional"))
      (node (ref "JP5") (pin "4") (pinfunction "4_4") (pintype "passive"))
    )
    (net (code "45") (name "/TXD5") (class "Default")
      (node (ref "D2") (pin "4") (pinfunction "4_4") (pintype "passive"))
      (node (ref "IC1") (pin "116") (pinfunction "PD2_116") (pintype "bidirectional"))
      (node (ref "JP4") (pin "1") (pinfunction "1_1") (pintype "passive"))
    )
    (net (code "46") (name "/U") (class "Default")
      (node (ref "IC1") (pin "36") (pinfunction "PA2_36") (pintype "bidirectional"))
      (node (ref "P4") (pin "2") (pinfunction "2_2") (pintype "passive"))
      (node (ref "P4") (pin "4") (pinfunction "4_4") (pintype "passive"))
    )
    (net (code "47") (name "/U_CV") (class "Default")
      (node (ref "IC1") (pin "43") (pinfunction "PA7_43") (pintype "bidirectional"))
      (node (ref "P4") (pin "10") (pinfunction "10_10") (pintype "passive"))
    )
    (net (code "48") (name "/VCAP2") (class "Default")
      (node (ref "IC1") (pin "106") (pinfunction "VCAP2_106") (pintype "power_in"))
    )
    (net (code "49") (name "GND") (class "Default")
      (node (ref "C1") (pin "2") (pinfunction "2_2") (pintype "passive"))
      (node (ref "C12") (pin "2") (pinfunction "2_2") (pintype "passive"))
      (node (ref "C13") (pin "2") (pinfunction "2_2") (pintype "passive"))
      (node (ref "C14") (pin "2") (pinfunction "2_2") (pintype "passive"))
      (node (ref "C18") (pin "2") (pinfunction "2_2") (pintype "passive"))
      (node (ref "C2") (pin "2") (pinfunction "2_2") (pintype "passive"))
      (node (ref "C22") (pin "2") (pinfunction "2_2") (pintype "passive"))
      (node (ref "C23") (pin "2") (pinfunction "2_2") (pintype "passive"))
      (node (ref "C24") (pin "2") (pinfunction "2_2") (pintype "passive"))
      (node (ref "C25") (pin "2") (pinfunction "2_2") (pintype "passive"))
      (node (ref "C26") (pin "2") (pinfunction "2_2") (pintype "passive"))
      (node (ref "C27") (pin "2") (pinfunction "2_2") (pintype "passive"))
      (node (ref "C28") (pin "2") (pinfunction "2_2") (pintype "passive"))
      (node (ref "C29") (pin "2") (pinfunction "2_2") (pintype "passive"))
      (node (ref "C3") (pin "2") (pinfunction "2_2") (pintype "passive"))
      (node (ref "C30") (pin "2") (pinfunction "2_2") (pintype "passive"))
      (node (ref "C31") (pin "2") (pinfunction "2_2") (pintype "passive"))
      (node (ref "C32") (pin "2") (pinfunction "2_2") (pintype "passive"))
      (node (ref "C33") (pin "1") (pinfunction "1_1") (pintype "passive"))
      (node (ref "C34") (pin "2") (pinfunction "2_2") (pintype "passive"))
      (node (ref "C35") (pin "2") (pinfunction "2_2") (pintype "passive"))
      (node (ref "C36") (pin "1") (pinfunction "1_1") (pintype "passive"))
      (node (ref "C37") (pin "2") (pinfunction "2_2") (pintype "passive"))
      (node (ref "C40") (pin "2") (pinfunction "2_2") (pintype "passive"))
      (node (ref "C41") (pin "1") (pinfunction "1_1") (pintype "passive"))
      (node (ref "C5") (pin "2") (pinfunction "2_2") (pintype "passive"))
      (node (ref "C54") (pin "1") (pinfunction "1_1") (pintype "passive"))
      (node (ref "C6") (pin "-") (pinfunction "-_-") (pintype "passive"))
      (node (ref "C7") (pin "2") (pinfunction "2_2") (pintype "passive"))
      (node (ref "D2") (pin "2") (pinfunction "2_2") (pintype "passive"))
      (node (ref "IC1") (pin "107") (pinfunction "VSS_107") (pintype "power_in"))
      (node (ref "IC1") (pin "120") (pinfunction "VSS_120") (pintype "power_in"))
      (node (ref "IC1") (pin "130") (pinfunction "VSS_130") (pintype "power_in"))
      (node (ref "IC1") (pin "143") (pinfunction "PDR_ON_143") (pintype "input"))
      (node (ref "IC1") (pin "16") (pinfunction "VSS_16") (pintype "power_in"))
      (node (ref "IC1") (pin "30") (pinfunction "VDD_30") (pintype "power_in"))
      (node (ref "IC1") (pin "31") (pinfunction "VSSA_31") (pintype "power_in"))
      (node (ref "IC1") (pin "38") (pinfunction "VSS_38") (pintype "power_in"))
      (node (ref "IC1") (pin "51") (pinfunction "VSS_51") (pintype "power_in"))
      (node (ref "IC1") (pin "61") (pinfunction "VSS_61") (pintype "power_in"))
      (node (ref "IC1") (pin "71") (pinfunction "VCAP1_71") (pintype "power_in"))
      (node (ref "IC1") (pin "83") (pinfunction "VSS_83") (pintype "power_in"))
      (node (ref "IC1") (pin "94") (pinfunction "VSS_94") (pintype "power_in"))
      (node (ref "IC2") (pin "5") (pinfunction "ERROR_5") (pintype "output"))
      (node (ref "IC2") (pin "6") (pinfunction "VTAB_6") (pintype "input"))
      (node (ref "IC2") (pin "7") (pinfunction "FEEDB_7") (pintype "output"))
      (node (ref "IC2") (pin "8") (pinfunction "INPUT_8") (pintype "passive"))
      (node (ref "J1") (pin "5") (pinfunction "5_5") (pintype "passive"))
      (node (ref "J1") (pin "S1") (pinfunction "SHIELD_S1") (pintype "passive"))
      (node (ref "J1") (pin "S2") (pinfunction "SHIELD_S2") (pintype "passive"))
      (node (ref "J1") (pin "S3") (pinfunction "SHIELD_S3") (pintype "passive"))
      (node (ref "J1") (pin "S4") (pinfunction "SHIELD_S4") (pintype "passive"))
      (node (ref "J1") (pin "S5") (pinfunction "SHIELD_S5") (pintype "passive"))
      (node (ref "J1") (pin "S6") (pinfunction "SHIELD_S6") (pintype "passive"))
      (node (ref "JP1") (pin "1") (pinfunction "1_1") (pintype "passive"))
      (node (ref "JP1") (pin "2") (pinfunction "2_2") (pintype "passive"))
      (node (ref "JP2") (pin "1") (pinfunction "1_1") (pintype "passive"))
      (node (ref "JP4") (pin "2") (pinfunction "2_2") (pintype "passive"))
      (node (ref "JP5") (pin "1") (pinfunction "1_1") (pintype "passive"))
      (node (ref "JP5") (pin "13") (pinfunction "13_13") (pintype "passive"))
      (node (ref "JP5") (pin "14") (pinfunction "14_14") (pintype "passive"))
      (node (ref "JP5") (pin "18") (pinfunction "18_18") (pintype "passive"))
      (node (ref "JP5") (pin "2") (pinfunction "2_2") (pintype "passive"))
      (node (ref "JP5") (pin "23") (pinfunction "23_23") (pintype "passive"))
      (node (ref "JP5") (pin "24") (pinfunction "24_24") (pintype "passive"))
      (node (ref "JP5") (pin "7") (pinfunction "7_7") (pintype "passive"))
      (node (ref "JP5") (pin "8") (pinfunction "8_8") (pintype "passive"))
      (node (ref "JP6") (pin "1") (pinfunction "1_1") (pintype "passive"))
      (node (ref "JP6") (pin "2") (pinfunction "2_2") (pintype "passive"))
      (node (ref "JP6") (pin "5") (pinfunction "5_5") (pintype "passive"))
      (node (ref "JP6") (pin "6") (pinfunction "6_6") (pintype "passive"))
      (node (ref "JP7") (pin "1") (pinfunction "1_1") (pintype "passive"))
      (node (ref "JP7") (pin "2") (pinfunction "2_2") (pintype "passive"))
      (node (ref "P2") (pin "4") (pinfunction "4_4") (pintype "passive"))
      (node (ref "P2") (pin "6") (pinfunction "6_6") (pintype "passive"))
      (node (ref "P2") (pin "8") (pinfunction "8_8") (pintype "passive"))
      (node (ref "P7") (pin "10") (pinfunction "10_10") (pintype "passive"))
      (node (ref "P7") (pin "12") (pinfunction "12_12") (pintype "passive"))
      (node (ref "P7") (pin "14") (pinfunction "14_14") (pintype "passive"))
      (node (ref "P7") (pin "16") (pinfunction "16_16") (pintype "passive"))
      (node (ref "P7") (pin "18") (pinfunction "18_18") (pintype "passive"))
      (node (ref "P7") (pin "20") (pinfunction "20_20") (pintype "passive"))
      (node (ref "P7") (pin "4") (pinfunction "4_4") (pintype "passive"))
      (node (ref "P7") (pin "6") (pinfunction "6_6") (pintype "passive"))
      (node (ref "P7") (pin "8") (pinfunction "8_8") (pintype "passive"))
      (node (ref "S1") (pin "1") (pinfunction "1_1") (pintype "passive"))
      (node (ref "S1") (pin "2") (pinfunction "2_2") (pintype "passive"))
      (node (ref "S2") (pin "1") (pinfunction "1_1") (pintype "passive"))
      (node (ref "S2") (pin "2") (pinfunction "2_2") (pintype "passive"))
      (node (ref "STF202-22TIG") (pin "6") (pinfunction "GND_6") (pintype "bidirectional"))
    )
    (net (code "50") (name "NRST") (class "Default")
      (node (ref "C40") (pin "1") (pinfunction "1_1") (pintype "passive"))
      (node (ref "IC1") (pin "25") (pinfunction "NRST_25") (pintype "bidirectional"))
      (node (ref "P7") (pin "15") (pinfunction "15_15") (pintype "passive"))
      (node (ref "S2") (pin "3") (pinfunction "3_3") (pintype "passive"))
      (node (ref "S2") (pin "4") (pinfunction "4_4") (pintype "passive"))
    )
    (net (code "51") (name "Net-(C4-Pad2)") (class "Default")
      (node (ref "C4") (pin "2") (pinfunction "2_2") (pintype "passive"))
      (node (ref "R25") (pin "2") (pinfunction "2_2") (pintype "passive"))
    )
    (net (code "52") (name "Net-(C18-Pad1)") (class "Default")
      (node (ref "C18") (pin "1") (pinfunction "1_1") (pintype "passive"))
      (node (ref "R5") (pin "2") (pinfunction "2_2") (pintype "passive"))
      (node (ref "Y1") (pin "1") (pinfunction "1_1") (pintype "bidirectional"))
    )
    (net (code "53") (name "Net-(IC1A-VBAT)") (class "Default")
      (node (ref "IC1") (pin "6") (pinfunction "VBAT_6") (pintype "power_in"))
      (node (ref "JP3") (pin "2") (pinfunction "2_2") (pintype "passive"))
    )
    (net (code "54") (name "Net-(IC1A-VDDA)") (class "Default")
      (node (ref "C54") (pin "2") (pinfunction "2_2") (pintype "passive"))
      (node (ref "IC1") (pin "33") (pinfunction "VDDA_33") (pintype "power_in"))
      (node (ref "L1") (pin "1") (pinfunction "1_1") (pintype "passive"))
    )
    (net (code "55") (name "Net-(IC2-GND)") (class "Default")
      (node (ref "C7") (pin "1") (pinfunction "1_1") (pintype "passive"))
      (node (ref "IC2") (pin "4") (pinfunction "GND_4") (pintype "power_in"))
    )
    (net (code "56") (name "Net-(IC2-SHDN)") (class "Default")
      (node (ref "C6") (pin "+") (pinfunction "+_+") (pintype "passive"))
      (node (ref "IC2") (pin "3") (pinfunction "SHDN_3") (pintype "input"))
      (node (ref "L3") (pin "1") (pinfunction "1_1") (pintype "passive"))
    )
    (net (code "57") (name "Net-(JP2-Pad2)") (class "Default")
      (node (ref "JP2") (pin "2") (pinfunction "2_2") (pintype "passive"))
      (node (ref "R22") (pin "1") (pinfunction "1_1") (pintype "passive"))
    )
    (net (code "58") (name "Net-(L6-Pad2)") (class "Default")
      (node (ref "L6") (pin "2") (pinfunction "2_2") (pintype "passive"))
      (node (ref "R23") (pin "1") (pinfunction "1_1") (pintype "passive"))
    )
    (net (code "59") (name "Net-(LD1-PadC)") (class "Default")
      (node (ref "LD1") (pin "C") (pinfunction "C_C") (pintype "passive"))
      (node (ref "R26") (pin "2") (pinfunction "2_2") (pintype "passive"))
    )
    (net (code "60") (name "Net-(LD2-PadC)") (class "Default")
      (node (ref "LD2") (pin "C") (pinfunction "C_C") (pintype "passive"))
      (node (ref "R27") (pin "2") (pinfunction "2_2") (pintype "passive"))
    )
    (net (code "61") (name "Net-(LD3-PadC)") (class "Default")
      (node (ref "LD3") (pin "C") (pinfunction "C_C") (pintype "passive"))
      (node (ref "R28") (pin "2") (pinfunction "2_2") (pintype "passive"))
    )
    (net (code "62") (name "Net-(LD4-PadC)") (class "Default")
      (node (ref "LD4") (pin "C") (pinfunction "C_C") (pintype "passive"))
      (node (ref "R29") (pin "2") (pinfunction "2_2") (pintype "passive"))
    )
    (net (code "63") (name "Net-(LD5-PadC)") (class "Default")
      (node (ref "LD5") (pin "C") (pinfunction "C_C") (pintype "passive"))
      (node (ref "R30") (pin "2") (pinfunction "2_2") (pintype "passive"))
    )
    (net (code "64") (name "Net-(P2-Pad1)") (class "Default")
      (node (ref "P2") (pin "1") (pinfunction "1_1") (pintype "passive"))
      (node (ref "R18") (pin "1") (pinfunction "1_1") (pintype "passive"))
    )
    (net (code "65") (name "Net-(P2-Pad3)") (class "Default")
      (node (ref "P2") (pin "3") (pinfunction "3_3") (pintype "passive"))
      (node (ref "R19") (pin "1") (pinfunction "1_1") (pintype "passive"))
    )
    (net (code "66") (name "Net-(P2-Pad5)") (class "Default")
      (node (ref "P2") (pin "5") (pinfunction "5_5") (pintype "passive"))
      (node (ref "R20") (pin "1") (pinfunction "1_1") (pintype "passive"))
    )
    (net (code "67") (name "SPI2_MISO") (class "Default")
      (node (ref "IC1") (pin "75") (pinfunction "PB14_75") (pintype "bidirectional"))
      (node (ref "JP5") (pin "17") (pinfunction "17_17") (pintype "passive"))
    )
    (net (code "68") (name "SPI2_MOSI") (class "Default")
      (node (ref "IC1") (pin "76") (pinfunction "PB15_76") (pintype "bidirectional"))
      (node (ref "JP5") (pin "16") (pinfunction "16_16") (pintype "passive"))
    )
    (net (code "69") (name "SPI3_MISO") (class "Default")
      (node (ref "IC1") (pin "134") (pinfunction "PB4_134") (pintype "bidirectional"))
      (node (ref "R20") (pin "2") (pinfunction "2_2") (pintype "passive"))
    )
    (net (code "70") (name "SPI3_MOSI") (class "Default")
      (node (ref "IC1") (pin "135") (pinfunction "PB5_135") (pintype "bidirectional"))
      (node (ref "R19") (pin "2") (pinfunction "2_2") (pintype "passive"))
    )
    (net (code "71") (name "SPI3_SCK") (class "Default")
      (node (ref "IC1") (pin "133") (pinfunction "PB3_133") (pintype "bidirectional"))
      (node (ref "R18") (pin "2") (pinfunction "2_2") (pintype "passive"))
    )
    (net (code "72") (name "VBUS") (class "Default")
      (node (ref "C36") (pin "2") (pinfunction "2_2") (pintype "passive"))
      (node (ref "D1") (pin "2") (pinfunction "ANODE_2") (pintype "passive"))
      (node (ref "L6") (pin "1") (pinfunction "1_1") (pintype "passive"))
      (node (ref "STF202-22TIG") (pin "1") (pinfunction "VCC_1") (pintype "bidirectional"))
    )
    (net (code "73") (name "VBUS_IN") (class "Default")
      (node (ref "J1") (pin "1") (pinfunction "1_1") (pintype "passive"))
      (node (ref "R23") (pin "2") (pinfunction "2_2") (pintype "passive"))
    )
    (net (code "74") (name "unconnected-(D2-Pad1)") (class "Default")
      (node (ref "D2") (pin "1") (pinfunction "1_1") (pintype "passive"))
    )
    (net (code "75") (name "unconnected-(IC1A-PA1-Pad35)") (class "Default")
      (node (ref "IC1") (pin "35") (pinfunction "PA1_35") (pintype "bidirectional"))
    )
    (net (code "76") (name "unconnected-(IC1A-PA3-Pad37)") (class "Default")
      (node (ref "IC1") (pin "37") (pinfunction "PA3_37") (pintype "bidirectional"))
    )
    (net (code "77") (name "unconnected-(IC1A-PA9-Pad101)") (class "Default")
      (node (ref "IC1") (pin "101") (pinfunction "PA9_101") (pintype "bidirectional"))
    )
    (net (code "78") (name "unconnected-(IC1A-PA10-Pad102)") (class "Default")
      (node (ref "IC1") (pin "102") (pinfunction "PA10_102") (pintype "bidirectional"))
    )
    (net (code "79") (name "unconnected-(IC1A-PA15-Pad110)") (class "Default")
      (node (ref "IC1") (pin "110") (pinfunction "PA15_110") (pintype "bidirectional"))
    )
    (net (code "80") (name "unconnected-(IC1A-PB0-Pad46)") (class "Default")
      (node (ref "IC1") (pin "46") (pinfunction "PB0_46") (pintype "bidirectional"))
    )
    (net (code "81") (name "unconnected-(IC1A-PB1-Pad47)") (class "Default")
      (node (ref "IC1") (pin "47") (pinfunction "PB1_47") (pintype "bidirectional"))
    )
    (net (code "82") (name "unconnected-(IC1A-PB2-Pad48)") (class "Default")
      (node (ref "IC1") (pin "48") (pinfunction "PB2_48") (pintype "bidirectional"))
    )
    (net (code "83") (name "unconnected-(IC1A-PB8-Pad139)") (class "Default")
      (node (ref "IC1") (pin "139") (pinfunction "PB8_139") (pintype "bidirectional"))
    )
    (net (code "84") (name "unconnected-(IC1A-PB9-Pad140)") (class "Default")
      (node (ref "IC1") (pin "140") (pinfunction "PB9_140") (pintype "bidirectional"))
    )
    (net (code "85") (name "unconnected-(IC1A-PB10-Pad69)") (class "Default")
      (node (ref "IC1") (pin "69") (pinfunction "PB10_69") (pintype "bidirectional"))
    )
    (net (code "86") (name "unconnected-(IC1A-PB11-Pad70)") (class "Default")
      (node (ref "IC1") (pin "70") (pinfunction "PB11_70") (pintype "bidirectional"))
    )
    (net (code "87") (name "unconnected-(IC1A-PB12-Pad73)") (class "Default")
      (node (ref "IC1") (pin "73") (pinfunction "PB12_73") (pintype "bidirectional"))
    )
    (net (code "88") (name "unconnected-(IC1A-PB13-Pad74)") (class "Default")
      (node (ref "IC1") (pin "74") (pinfunction "PB13_74") (pintype "bidirectional"))
    )
    (net (code "89") (name "unconnected-(IC1A-PC0-Pad26)") (class "Default")
      (node (ref "IC1") (pin "26") (pinfunction "PC0_26") (pintype "bidirectional"))
    )
    (net (code "90") (name "unconnected-(IC1A-PC1-Pad27)") (class "Default")
      (node (ref "IC1") (pin "27") (pinfunction "PC1_27") (pintype "bidirectional"))
    )
    (net (code "91") (name "unconnected-(IC1A-PC2-Pad28)") (class "Default")
      (node (ref "IC1") (pin "28") (pinfunction "PC2_28") (pintype "bidirectional"))
    )
    (net (code "92") (name "unconnected-(IC1A-PC3-Pad29)") (class "Default")
      (node (ref "IC1") (pin "29") (pinfunction "PC3_29") (pintype "bidirectional"))
    )
    (net (code "93") (name "unconnected-(IC1A-PC6-Pad96)") (class "Default")
      (node (ref "IC1") (pin "96") (pinfunction "PC6_96") (pintype "bidirectional"))
    )
    (net (code "94") (name "unconnected-(IC1A-PC7-Pad97)") (class "Default")
      (node (ref "IC1") (pin "97") (pinfunction "PC7_97") (pintype "bidirectional"))
    )
    (net (code "95") (name "unconnected-(IC1A-PC9-Pad99)") (class "Default")
      (node (ref "IC1") (pin "99") (pinfunction "PC9_99") (pintype "bidirectional"))
    )
    (net (code "96") (name "unconnected-(IC1A-PC10-Pad111)") (class "Default")
      (node (ref "IC1") (pin "111") (pinfunction "PC10_111") (pintype "bidirectional"))
    )
    (net (code "97") (name "unconnected-(IC1A-PC11-Pad112)") (class "Default")
      (node (ref "IC1") (pin "112") (pinfunction "PC11_112") (pintype "bidirectional"))
    )
    (net (code "98") (name "unconnected-(IC1A-PD0-Pad114)") (class "Default")
      (node (ref "IC1") (pin "114") (pinfunction "PD0_114") (pintype "bidirectional"))
    )
    (net (code "99") (name "unconnected-(IC1A-PD1-Pad115)") (class "Default")
      (node (ref "IC1") (pin "115") (pinfunction "PD1_115") (pintype "bidirectional"))
    )
    (net (code "100") (name "unconnected-(IC1A-PD3-Pad117)") (class "Default")
      (node (ref "IC1") (pin "117") (pinfunction "PD3_117") (pintype "bidirectional"))
    )
    (net (code "101") (name "unconnected-(IC1A-PD4-Pad118)") (class "Default")
      (node (ref "IC1") (pin "118") (pinfunction "PD4_118") (pintype "bidirectional"))
    )
    (net (code "102") (name "unconnected-(IC1A-PD5-Pad119)") (class "Default")
      (node (ref "IC1") (pin "119") (pinfunction "PD5_119") (pintype "bidirectional"))
    )
    (net (code "103") (name "unconnected-(IC1A-PD11-Pad80)") (class "Default")
      (node (ref "IC1") (pin "80") (pinfunction "PD11_80") (pintype "bidirectional"))
    )
    (net (code "104") (name "unconnected-(IC1A-PD12-Pad81)") (class "Default")
      (node (ref "IC1") (pin "81") (pinfunction "PD12_81") (pintype "bidirectional"))
    )
    (net (code "105") (name "unconnected-(IC1A-PD15-Pad86)") (class "Default")
      (node (ref "IC1") (pin "86") (pinfunction "PD15_86") (pintype "bidirectional"))
    )
    (net (code "106") (name "unconnected-(IC1A-PE0-Pad141)") (class "Default")
      (node (ref "IC1") (pin "141") (pinfunction "PE0_141") (pintype "bidirectional"))
    )
    (net (code "107") (name "unconnected-(IC1A-PE1-Pad142)") (class "Default")
      (node (ref "IC1") (pin "142") (pinfunction "PE1_142") (pintype "bidirectional"))
    )
    (net (code "108") (name "unconnected-(IC1A-PE2-Pad1)") (class "Default")
      (node (ref "IC1") (pin "1") (pinfunction "PE2_1") (pintype "bidirectional"))
    )
    (net (code "109") (name "unconnected-(IC1A-PE3-Pad2)") (class "Default")
      (node (ref "IC1") (pin "2") (pinfunction "PE3_2") (pintype "bidirectional"))
    )
    (net (code "110") (name "unconnected-(IC1A-PE4-Pad3)") (class "Default")
      (node (ref "IC1") (pin "3") (pinfunction "PE4_3") (pintype "bidirectional"))
    )
    (net (code "111") (name "unconnected-(IC1A-PE5-Pad4)") (class "Default")
      (node (ref "IC1") (pin "4") (pinfunction "PE5_4") (pintype "bidirectional"))
    )
    (net (code "112") (name "unconnected-(IC1A-PE6-Pad5)") (class "Default")
      (node (ref "IC1") (pin "5") (pinfunction "PE6_5") (pintype "bidirectional"))
    )
    (net (code "113") (name "unconnected-(IC1A-PE7-Pad58)") (class "Default")
      (node (ref "IC1") (pin "58") (pinfunction "PE7_58") (pintype "bidirectional"))
    )
    (net (code "114") (name "unconnected-(IC1A-PE8-Pad59)") (class "Default")
      (node (ref "IC1") (pin "59") (pinfunction "PE8_59") (pintype "bidirectional"))
    )
    (net (code "115") (name "unconnected-(IC1A-PE9-Pad60)") (class "Default")
      (node (ref "IC1") (pin "60") (pinfunction "PE9_60") (pintype "bidirectional"))
    )
    (net (code "116") (name "unconnected-(IC1A-PE15-Pad68)") (class "Default")
      (node (ref "IC1") (pin "68") (pinfunction "PE15_68") (pintype "bidirectional"))
    )
    (net (code "117") (name "unconnected-(IC1A-PF0-Pad10)") (class "Default")
      (node (ref "IC1") (pin "10") (pinfunction "PF0_10") (pintype "bidirectional"))
    )
    (net (code "118") (name "unconnected-(IC1A-PF1-Pad11)") (class "Default")
      (node (ref "IC1") (pin "11") (pinfunction "PF1_11") (pintype "bidirectional"))
    )
    (net (code "119") (name "unconnected-(IC1A-PF2-Pad12)") (class "Default")
      (node (ref "IC1") (pin "12") (pinfunction "PF2_12") (pintype "bidirectional"))
    )
    (net (code "120") (name "unconnected-(IC1A-PF3-Pad13)") (class "Default")
      (node (ref "IC1") (pin "13") (pinfunction "PF3_13") (pintype "bidirectional"))
    )
    (net (code "121") (name "unconnected-(IC1A-PF4-Pad14)") (class "Default")
      (node (ref "IC1") (pin "14") (pinfunction "PF4_14") (pintype "bidirectional"))
    )
    (net (code "122") (name "unconnected-(IC1A-PF5-Pad15)") (class "Default")
      (node (ref "IC1") (pin "15") (pinfunction "PF5_15") (pintype "bidirectional"))
    )
    (net (code "123") (name "unconnected-(IC1A-PF6-Pad18)") (class "Default")
      (node (ref "IC1") (pin "18") (pinfunction "PF6_18") (pintype "bidirectional"))
    )
    (net (code "124") (name "unconnected-(IC1A-PF7-Pad19)") (class "Default")
      (node (ref "IC1") (pin "19") (pinfunction "PF7_19") (pintype "bidirectional"))
    )
    (net (code "125") (name "unconnected-(IC1A-PF8-Pad20)") (class "Default")
      (node (ref "IC1") (pin "20") (pinfunction "PF8_20") (pintype "bidirectional"))
    )
    (net (code "126") (name "unconnected-(IC1A-PF10-Pad22)") (class "Default")
      (node (ref "IC1") (pin "22") (pinfunction "PF10_22") (pintype "bidirectional"))
    )
    (net (code "127") (name "unconnected-(IC1A-PF11-Pad49)") (class "Default")
      (node (ref "IC1") (pin "49") (pinfunction "PF11_49") (pintype "bidirectional"))
    )
    (net (code "128") (name "unconnected-(IC1A-PF12-Pad50)") (class "Default")
      (node (ref "IC1") (pin "50") (pinfunction "PF12_50") (pintype "bidirectional"))
    )
    (net (code "129") (name "unconnected-(IC1A-PF13-Pad53)") (class "Default")
      (node (ref "IC1") (pin "53") (pinfunction "PF13_53") (pintype "bidirectional"))
    )
    (net (code "130") (name "unconnected-(IC1A-PF14-Pad54)") (class "Default")
      (node (ref "IC1") (pin "54") (pinfunction "PF14_54") (pintype "bidirectional"))
    )
    (net (code "131") (name "unconnected-(IC1A-PF15-Pad55)") (class "Default")
      (node (ref "IC1") (pin "55") (pinfunction "PF15_55") (pintype "bidirectional"))
    )
    (net (code "132") (name "unconnected-(IC1A-PG0-Pad56)") (class "Default")
      (node (ref "IC1") (pin "56") (pinfunction "PG0_56") (pintype "bidirectional"))
    )
    (net (code "133") (name "unconnected-(IC1A-PG1-Pad57)") (class "Default")
      (node (ref "IC1") (pin "57") (pinfunction "PG1_57") (pintype "bidirectional"))
    )
    (net (code "134") (name "unconnected-(IC1A-PG2-Pad87)") (class "Default")
      (node (ref "IC1") (pin "87") (pinfunction "PG2_87") (pintype "bidirectional"))
    )
    (net (code "135") (name "unconnected-(IC1A-PG3-Pad88)") (class "Default")
      (node (ref "IC1") (pin "88") (pinfunction "PG3_88") (pintype "bidirectional"))
    )
    (net (code "136") (name "unconnected-(IC1A-PG4-Pad89)") (class "Default")
      (node (ref "IC1") (pin "89") (pinfunction "PG4_89") (pintype "bidirectional"))
    )
    (net (code "137") (name "unconnected-(IC1A-PG5-Pad90)") (class "Default")
      (node (ref "IC1") (pin "90") (pinfunction "PG5_90") (pintype "bidirectional"))
    )
    (net (code "138") (name "unconnected-(IC1A-PG6-Pad91)") (class "Default")
      (node (ref "IC1") (pin "91") (pinfunction "PG6_91") (pintype "bidirectional"))
    )
    (net (code "139") (name "unconnected-(IC1A-PG7-Pad92)") (class "Default")
      (node (ref "IC1") (pin "92") (pinfunction "PG7_92") (pintype "bidirectional"))
    )
    (net (code "140") (name "unconnected-(IC1A-PG8-Pad93)") (class "Default")
      (node (ref "IC1") (pin "93") (pinfunction "PG8_93") (pintype "bidirectional"))
    )
    (net (code "141") (name "unconnected-(IC1A-PG11-Pad126)") (class "Default")
      (node (ref "IC1") (pin "126") (pinfunction "PG11_126") (pintype "bidirectional"))
    )
    (net (code "142") (name "unconnected-(IC1A-PG12-Pad127)") (class "Default")
      (node (ref "IC1") (pin "127") (pinfunction "PG12_127") (pintype "bidirectional"))
    )
    (net (code "143") (name "unconnected-(IC1A-PG13-Pad128)") (class "Default")
      (node (ref "IC1") (pin "128") (pinfunction "PG13_128") (pintype "bidirectional"))
    )
    (net (code "144") (name "unconnected-(IC1A-PG14-Pad129)") (class "Default")
      (node (ref "IC1") (pin "129") (pinfunction "PG14_129") (pintype "bidirectional"))
    )
    (net (code "145") (name "unconnected-(IC1A-PG15-Pad132)") (class "Default")
      (node (ref "IC1") (pin "132") (pinfunction "PG15_132") (pintype "bidirectional"))
    )
    (net (code "146") (name "unconnected-(J1-Pad4)") (class "Default")
      (node (ref "J1") (pin "4") (pinfunction "4_4") (pintype "passive"))
    )
    (net (code "147") (name "unconnected-(JP1-Pad7)") (class "Default")
      (node (ref "JP1") (pin "7") (pinfunction "7_7") (pintype "passive"))
    )
    (net (code "148") (name "unconnected-(JP1-Pad8)") (class "Default")
      (node (ref "JP1") (pin "8") (pinfunction "8_8") (pintype "passive"))
    )
    (net (code "149") (name "unconnected-(JP1-Pad13)") (class "Default")
      (node (ref "JP1") (pin "13") (pinfunction "13_13") (pintype "passive"))
    )
    (net (code "150") (name "unconnected-(JP1-Pad14)") (class "Default")
      (node (ref "JP1") (pin "14") (pinfunction "14_14") (pintype "passive"))
    )
    (net (code "151") (name "unconnected-(JP1-Pad19)") (class "Default")
      (node (ref "JP1") (pin "19") (pinfunction "19_19") (pintype "passive"))
    )
    (net (code "152") (name "unconnected-(JP1-Pad20)") (class "Default")
      (node (ref "JP1") (pin "20") (pinfunction "20_20") (pintype "passive"))
    )
    (net (code "153") (name "unconnected-(JP5-Pad5)") (class "Default")
      (node (ref "JP5") (pin "5") (pinfunction "5_5") (pintype "passive"))
    )
    (net (code "154") (name "unconnected-(JP5-Pad6)") (class "Default")
      (node (ref "JP5") (pin "6") (pinfunction "6_6") (pintype "passive"))
    )
    (net (code "155") (name "unconnected-(JP5-Pad9)") (class "Default")
      (node (ref "JP5") (pin "9") (pinfunction "9_9") (pintype "passive"))
    )
    (net (code "156") (name "unconnected-(JP5-Pad10)") (class "Default")
      (node (ref "JP5") (pin "10") (pinfunction "10_10") (pintype "passive"))
    )
    (net (code "157") (name "unconnected-(JP6-Pad3)") (class "Default")
      (node (ref "JP6") (pin "3") (pinfunction "3_3") (pintype "passive"))
    )
    (net (code "158") (name "unconnected-(P4-Pad1)") (class "Default")
      (node (ref "P4") (pin "1") (pinfunction "1_1") (pintype "passive"))
    )
    (net (code "159") (name "unconnected-(P4-Pad5)") (class "Default")
      (node (ref "P4") (pin "5") (pinfunction "5_5") (pintype "passive"))
    )
    (net (code "160") (name "unconnected-(P4-Pad9)") (class "Default")
      (node (ref "P4") (pin "9") (pinfunction "9_9") (pintype "passive"))
    )
    (net (code "161") (name "unconnected-(P7-Pad1)") (class "Default")
      (node (ref "P7") (pin "1") (pinfunction "1_1") (pintype "passive"))
    )
    (net (code "162") (name "unconnected-(P7-Pad2)") (class "Default")
      (node (ref "P7") (pin "2") (pinfunction "2_2") (pintype "passive"))
    )
    (net (code "163") (name "unconnected-(P7-Pad3)") (class "Default")
      (node (ref "P7") (pin "3") (pinfunction "3_3") (pintype "passive"))
    )
    (net (code "164") (name "unconnected-(P7-Pad5)") (class "Default")
      (node (ref "P7") (pin "5") (pinfunction "5_5") (pintype "passive"))
    )
    (net (code "165") (name "unconnected-(P7-Pad11)") (class "Default")
      (node (ref "P7") (pin "11") (pinfunction "11_11") (pintype "passive"))
    )
    (net (code "166") (name "unconnected-(P7-Pad13)") (class "Default")
      (node (ref "P7") (pin "13") (pinfunction "13_13") (pintype "passive"))
    )
    (net (code "167") (name "unconnected-(P7-Pad17)") (class "Default")
      (node (ref "P7") (pin "17") (pinfunction "17_17") (pintype "passive"))
    )
    (net (code "168") (name "unconnected-(P7-Pad19)") (class "Default")
      (node (ref "P7") (pin "19") (pinfunction "19_19") (pintype "passive"))
    )
  )
)
